# 07_EL_CON.net
KiCad netlist of a schematic drawn in Altium Designer
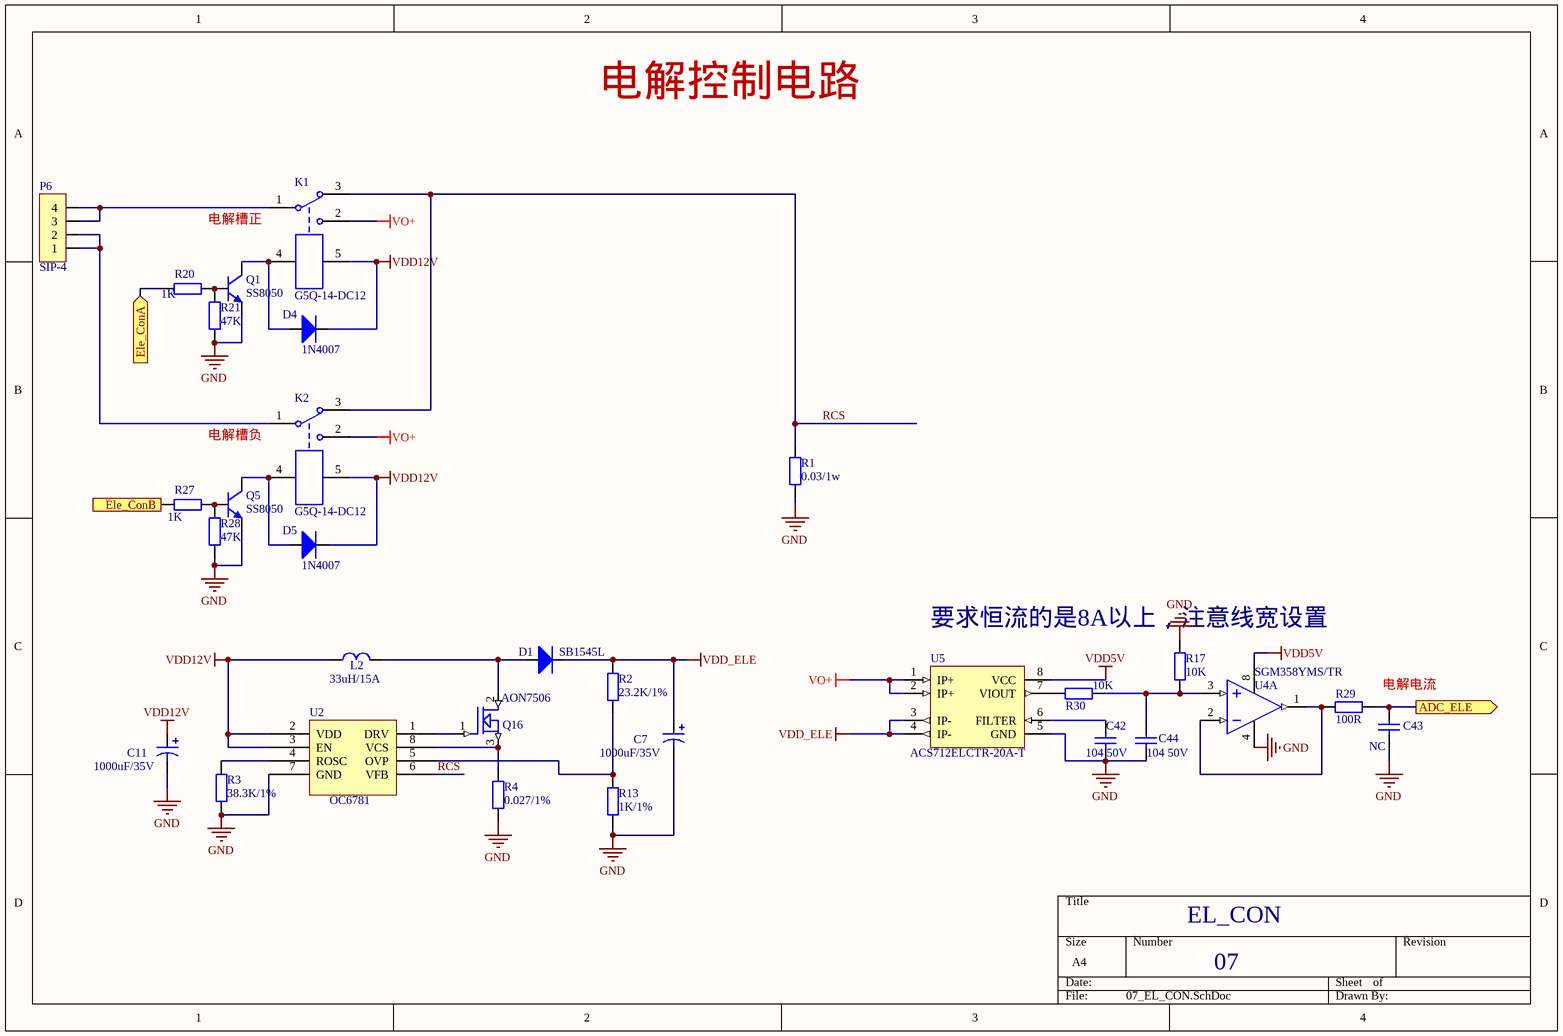
[diagram p0: 07_EL_CON.SchDoc]

(export (version "E")
  (design (tool "Eeschema 10.0.6"))
  (components
    (comp (ref "C7")
      (value "1000uF/35V")
      (footprint "10*16")
      (description "电解电容")
      (libsource (lib "XiaoyI") (part "CAP2"))
    )
    (comp (ref "C11")
      (value "1000uF/35V")
      (footprint "10*16")
      (description "电解电容")
      (libsource (lib "XiaoyI") (part "CAP2"))
    )
    (comp (ref "C42")
      (value "104 50V")
      (footprint "SMD-0603C")
      (description "贴片电容 10%")
      (libsource (lib "XiaoyI") (part "CAP4"))
    )
    (comp (ref "C43")
      (value "NC")
      (footprint "SMD-0603C")
      (description "贴片电容 10%")
      (libsource (lib "XiaoyI") (part "CAP4"))
    )
    (comp (ref "C44")
      (value "104 50V")
      (footprint "SMD-0603C")
      (description "贴片电容 10%")
      (libsource (lib "XiaoyI") (part "CAP4"))
    )
    (comp (ref "D1")
      (value "SB1545L")
      (footprint "TO227")
      (description "肖特基二极管")
      (libsource (lib "XiaoyI") (part "DIODE2"))
    )
    (comp (ref "D4")
      (value "1N4007")
      (footprint "DO-214-AC")
      (description "贴片二极管")
      (libsource (lib "XiaoyI") (part "DIODE2"))
    )
    (comp (ref "D5")
      (value "1N4007")
      (footprint "DO-214-AC")
      (description "贴片二极管")
      (libsource (lib "XiaoyI") (part "DIODE2"))
    )
    (comp (ref "K1")
      (value "G5Q-14-DC12")
      (footprint "G5Q-14")
      (description "5V 继电器")
      (libsource (lib "XiaoyI") (part "JDQ1"))
    )
    (comp (ref "K2")
      (value "G5Q-14-DC12")
      (footprint "G5Q-14")
      (description "5V 继电器")
      (libsource (lib "XiaoyI") (part "JDQ1"))
    )
    (comp (ref "L2")
      (value "33uH/15A")
      (footprint "INDUCTOR_34*18")
      (description "10uH 1A")
      (libsource (lib "XiaoyI") (part "Inductor1"))
    )
    (comp (ref "P6")
      (value "SIP-4")
      (footprint "VH-AW-3.96*4P")
      (description "3.96 4P 直插")
      (libsource (lib "XiaoyI") (part "SIP-4"))
    )
    (comp (ref "Q1")
      (value "SS8050")
      (footprint "SOT-23")
      (description "三极管")
      (libsource (lib "XiaoyI") (part "NPN-1"))
    )
    (comp (ref "Q5")
      (value "SS8050")
      (footprint "SOT-23")
      (description "三极管")
      (libsource (lib "XiaoyI") (part "NPN-1"))
    )
    (comp (ref "Q16")
      (value "AON7506")
      (footprint "DFN3*3-8")
      (description "MOSFET N")
      (libsource (lib "XiaoyI") (part "MOSFET N"))
    )
    (comp (ref "R1")
      (value "0.03/1w")
      (footprint "2512R")
      (description "贴片电阻 5%")
      (libsource (lib "") (part "RES2_1"))
    )
    (comp (ref "R2")
      (value "23.2K/1%")
      (footprint "SMD-0603")
      (description "贴片电阻 5%")
      (libsource (lib "") (part "RES2_1"))
    )
    (comp (ref "R3")
      (value "38.3K/1%")
      (footprint "SMD-0603")
      (description "贴片电阻 5%")
      (libsource (lib "") (part "RES2_1"))
    )
    (comp (ref "R4")
      (value "0.027/1%")
      (footprint "2512r")
      (description "贴片电阻 5%")
      (libsource (lib "") (part "RES2_1"))
    )
    (comp (ref "R13")
      (value "1K/1%")
      (footprint "SMD-0603")
      (description "贴片电阻 5%")
      (libsource (lib "") (part "RES2_1"))
    )
    (comp (ref "R17")
      (value "10K")
      (footprint "SMD-0603")
      (description "贴片电阻 1%")
      (libsource (lib "") (part "RES0_1"))
    )
    (comp (ref "R20")
      (value "1K")
      (footprint "SMD-0603")
      (description "贴片电阻 5%")
      (libsource (lib "") (part "RES2_2"))
    )
    (comp (ref "R21")
      (value "47K")
      (footprint "SMD-0603")
      (description "贴片电阻 5%")
      (libsource (lib "XiaoyI") (part "RES2"))
    )
    (comp (ref "R27")
      (value "1K")
      (footprint "SMD-0603")
      (description "贴片电阻 5%")
      (libsource (lib "") (part "RES2_2"))
    )
    (comp (ref "R28")
      (value "47K")
      (footprint "SMD-0603")
      (description "贴片电阻 5%")
      (libsource (lib "XiaoyI") (part "RES2"))
    )
    (comp (ref "R29")
      (value "100R")
      (footprint "SMD-0603")
      (description "贴片电阻 5%")
      (libsource (lib "ABB") (part "RES0"))
    )
    (comp (ref "R30")
      (value "10K")
      (footprint "SMD-0603")
      (description "贴片电阻 1%")
      (libsource (lib "ABB") (part "RES0"))
    )
    (comp (ref "U2")
      (value "OC6781")
      (footprint "SOP127P600X265_HS-9N")
      (libsource (lib "stm32") (part "OC6781"))
    )
    (comp (ref "U4")
      (value "SGM358YMS/TR")
      (footprint "MSOP-8")
      (description "运算放大器")
      (libsource (lib "XiaoyI") (part "LM358"))
    )
    (comp (ref "U5")
      (value "ACS712ELCTR-20A-T")
      (footprint "SO-8")
      (description "HALL 20A 电流传感器")
      (libsource (lib "XiaoyI") (part "ACS712"))
    )
  )
  (nets
    (net (code "1") (name "/ADC_ELE") (class "Default")
      (node (ref "C43") (pin "2") (pinfunction "2_2") (pintype "passive"))
      (node (ref "R29") (pin "1") (pinfunction "1_1") (pintype "passive"))
    )
    (net (code "2") (name "/Ele_ConA") (class "Default")
      (node (ref "R20") (pin "1") (pinfunction "1_1") (pintype "passive"))
    )
    (net (code "3") (name "/Ele_ConB") (class "Default")
      (node (ref "R27") (pin "1") (pinfunction "1_1") (pintype "passive"))
    )
    (net (code "4") (name "/RCS") (class "Default")
      (node (ref "K1") (pin "3") (pinfunction "3_3") (pintype "passive"))
      (node (ref "K2") (pin "3") (pinfunction "3_3") (pintype "passive"))
      (node (ref "R1") (pin "1") (pinfunction "1_1") (pintype "passive"))
      (node (ref "U2") (pin "6") (pinfunction "VFB_6") (pintype "passive"))
    )
    (net (code "5") (name "GND") (class "Default")
      (node (ref "C11") (pin "2") (pinfunction "2_2") (pintype "passive"))
      (node (ref "C42") (pin "2") (pinfunction "2_2") (pintype "passive"))
      (node (ref "C43") (pin "1") (pinfunction "1_1") (pintype "passive"))
      (node (ref "C44") (pin "2") (pinfunction "2_2") (pintype "passive"))
      (node (ref "C7") (pin "2") (pinfunction "2_2") (pintype "passive"))
      (node (ref "Q1") (pin "2") (pinfunction "E_2") (pintype "passive"))
      (node (ref "Q5") (pin "2") (pinfunction "E_2") (pintype "passive"))
      (node (ref "R1") (pin "2") (pinfunction "2_2") (pintype "passive"))
      (node (ref "R13") (pin "2") (pinfunction "2_2") (pintype "passive"))
      (node (ref "R17") (pin "1") (pinfunction "1_1") (pintype "passive"))
      (node (ref "R21") (pin "1") (pinfunction "1_1") (pintype "passive"))
      (node (ref "R28") (pin "1") (pinfunction "1_1") (pintype "passive"))
      (node (ref "R3") (pin "2") (pinfunction "2_2") (pintype "passive"))
      (node (ref "R4") (pin "2") (pinfunction "2_2") (pintype "passive"))
      (node (ref "U2") (pin "7") (pinfunction "GND_7") (pintype "passive"))
      (node (ref "U4") (pin "4") (pinfunction "V-_4") (pintype "power_in"))
      (node (ref "U5") (pin "5") (pinfunction "GND_5") (pintype "power_in"))
    )
    (net (code "6") (name "Net-(D1-A)") (class "Default")
      (node (ref "D1") (pin "1") (pinfunction "A_1") (pintype "passive"))
      (node (ref "L2") (pin "2") (pinfunction "2_2") (pintype "passive"))
      (node (ref "Q16") (pin "2") (pinfunction "D_2") (pintype "input"))
    )
    (net (code "7") (name "Net-(D4-A)") (class "Default")
      (node (ref "D4") (pin "1") (pinfunction "A_1") (pintype "passive"))
      (node (ref "K1") (pin "4") (pinfunction "4_4") (pintype "passive"))
      (node (ref "Q1") (pin "3") (pinfunction "C_3") (pintype "passive"))
    )
    (net (code "8") (name "Net-(D5-A)") (class "Default")
      (node (ref "D5") (pin "1") (pinfunction "A_1") (pintype "passive"))
      (node (ref "K2") (pin "4") (pinfunction "4_4") (pintype "passive"))
      (node (ref "Q5") (pin "3") (pinfunction "C_3") (pintype "passive"))
    )
    (net (code "9") (name "Net-(K1-Pad1)") (class "Default")
      (node (ref "K1") (pin "1") (pinfunction "1_1") (pintype "passive"))
      (node (ref "P6") (pin "3") (pinfunction "3_3") (pintype "passive"))
      (node (ref "P6") (pin "4") (pinfunction "4_4") (pintype "passive"))
    )
    (net (code "10") (name "Net-(K2-Pad1)") (class "Default")
      (node (ref "K2") (pin "1") (pinfunction "1_1") (pintype "passive"))
      (node (ref "P6") (pin "1") (pinfunction "1_1") (pintype "passive"))
      (node (ref "P6") (pin "2") (pinfunction "2_2") (pintype "passive"))
    )
    (net (code "11") (name "Net-(Q1-B)") (class "Default")
      (node (ref "Q1") (pin "1") (pinfunction "B_1") (pintype "passive"))
      (node (ref "R20") (pin "2") (pinfunction "2_2") (pintype "passive"))
      (node (ref "R21") (pin "2") (pinfunction "2_2") (pintype "passive"))
    )
    (net (code "12") (name "Net-(Q5-B)") (class "Default")
      (node (ref "Q5") (pin "1") (pinfunction "B_1") (pintype "passive"))
      (node (ref "R27") (pin "2") (pinfunction "2_2") (pintype "passive"))
      (node (ref "R28") (pin "2") (pinfunction "2_2") (pintype "passive"))
    )
    (net (code "13") (name "Net-(Q16-G)") (class "Default")
      (node (ref "Q16") (pin "1") (pinfunction "G_1") (pintype "input"))
      (node (ref "U2") (pin "1") (pinfunction "DRV_1") (pintype "passive"))
    )
    (net (code "14") (name "Net-(Q16-S)") (class "Default")
      (node (ref "Q16") (pin "3") (pinfunction "S_3") (pintype "output"))
      (node (ref "R4") (pin "1") (pinfunction "1_1") (pintype "passive"))
      (node (ref "U2") (pin "8") (pinfunction "VCS_8") (pintype "passive"))
    )
    (net (code "15") (name "Net-(U2-OVP)") (class "Default")
      (node (ref "R13") (pin "1") (pinfunction "1_1") (pintype "passive"))
      (node (ref "R2") (pin "2") (pinfunction "2_2") (pintype "passive"))
      (node (ref "U2") (pin "5") (pinfunction "OVP_5") (pintype "passive"))
    )
    (net (code "16") (name "Net-(U2-ROSC)") (class "Default")
      (node (ref "R3") (pin "1") (pinfunction "1_1") (pintype "passive"))
      (node (ref "U2") (pin "4") (pinfunction "ROSC_4") (pintype "passive"))
    )
    (net (code "17") (name "Net-(U4A-IN1+)") (class "Default")
      (node (ref "C44") (pin "1") (pinfunction "1_1") (pintype "passive"))
      (node (ref "R17") (pin "2") (pinfunction "2_2") (pintype "passive"))
      (node (ref "R30") (pin "1") (pinfunction "1_1") (pintype "passive"))
      (node (ref "U4") (pin "3") (pinfunction "IN1+_3") (pintype "input"))
    )
    (net (code "18") (name "Net-(U4A-IN1-)") (class "Default")
      (node (ref "R29") (pin "2") (pinfunction "2_2") (pintype "passive"))
      (node (ref "U4") (pin "1") (pinfunction "OUT1_1") (pintype "output"))
      (node (ref "U4") (pin "2") (pinfunction "IN1-_2") (pintype "input"))
    )
    (net (code "19") (name "Net-(U5-FILTER)") (class "Default")
      (node (ref "C42") (pin "1") (pinfunction "1_1") (pintype "passive"))
      (node (ref "U5") (pin "6") (pinfunction "FILTER_6") (pintype "input"))
    )
    (net (code "20") (name "Net-(U5-VIOUT)") (class "Default")
      (node (ref "R30") (pin "2") (pinfunction "2_2") (pintype "passive"))
      (node (ref "U5") (pin "7") (pinfunction "VIOUT_7") (pintype "output"))
    )
    (net (code "21") (name "VDD5V") (class "Default")
      (node (ref "U4") (pin "8") (pinfunction "V+_8") (pintype "power_in"))
      (node (ref "U5") (pin "8") (pinfunction "VCC_8") (pintype "power_in"))
    )
    (net (code "22") (name "VDD12V") (class "Default")
      (node (ref "C11") (pin "1") (pinfunction "1_1") (pintype "passive"))
      (node (ref "D4") (pin "2") (pinfunction "K_2") (pintype "passive"))
      (node (ref "D5") (pin "2") (pinfunction "K_2") (pintype "passive"))
      (node (ref "K1") (pin "5") (pinfunction "5_5") (pintype "passive"))
      (node (ref "K2") (pin "5") (pinfunction "5_5") (pintype "passive"))
      (node (ref "L2") (pin "1") (pinfunction "1_1") (pintype "passive"))
      (node (ref "U2") (pin "2") (pinfunction "VDD_2") (pintype "passive"))
      (node (ref "U2") (pin "3") (pinfunction "EN_3") (pintype "passive"))
    )
    (net (code "23") (name "VDD_ELE") (class "Default")
      (node (ref "C7") (pin "1") (pinfunction "1_1") (pintype "passive"))
      (node (ref "D1") (pin "2") (pinfunction "K_2") (pintype "passive"))
      (node (ref "R2") (pin "1") (pinfunction "1_1") (pintype "passive"))
      (node (ref "U5") (pin "3") (pinfunction "IP-_3") (pintype "output"))
      (node (ref "U5") (pin "4") (pinfunction "IP-_4") (pintype "output"))
    )
    (net (code "24") (name "VO+") (class "Default")
      (node (ref "K1") (pin "2") (pinfunction "2_2") (pintype "passive"))
      (node (ref "K2") (pin "2") (pinfunction "2_2") (pintype "passive"))
      (node (ref "U5") (pin "1") (pinfunction "IP+_1") (pintype "input"))
      (node (ref "U5") (pin "2") (pinfunction "IP+_2") (pintype "input"))
    )
  )
)
